# 3w-rgb-led-dongle-mk-1_0.net
KiCad netlist of a schematic drawn in EAGLE
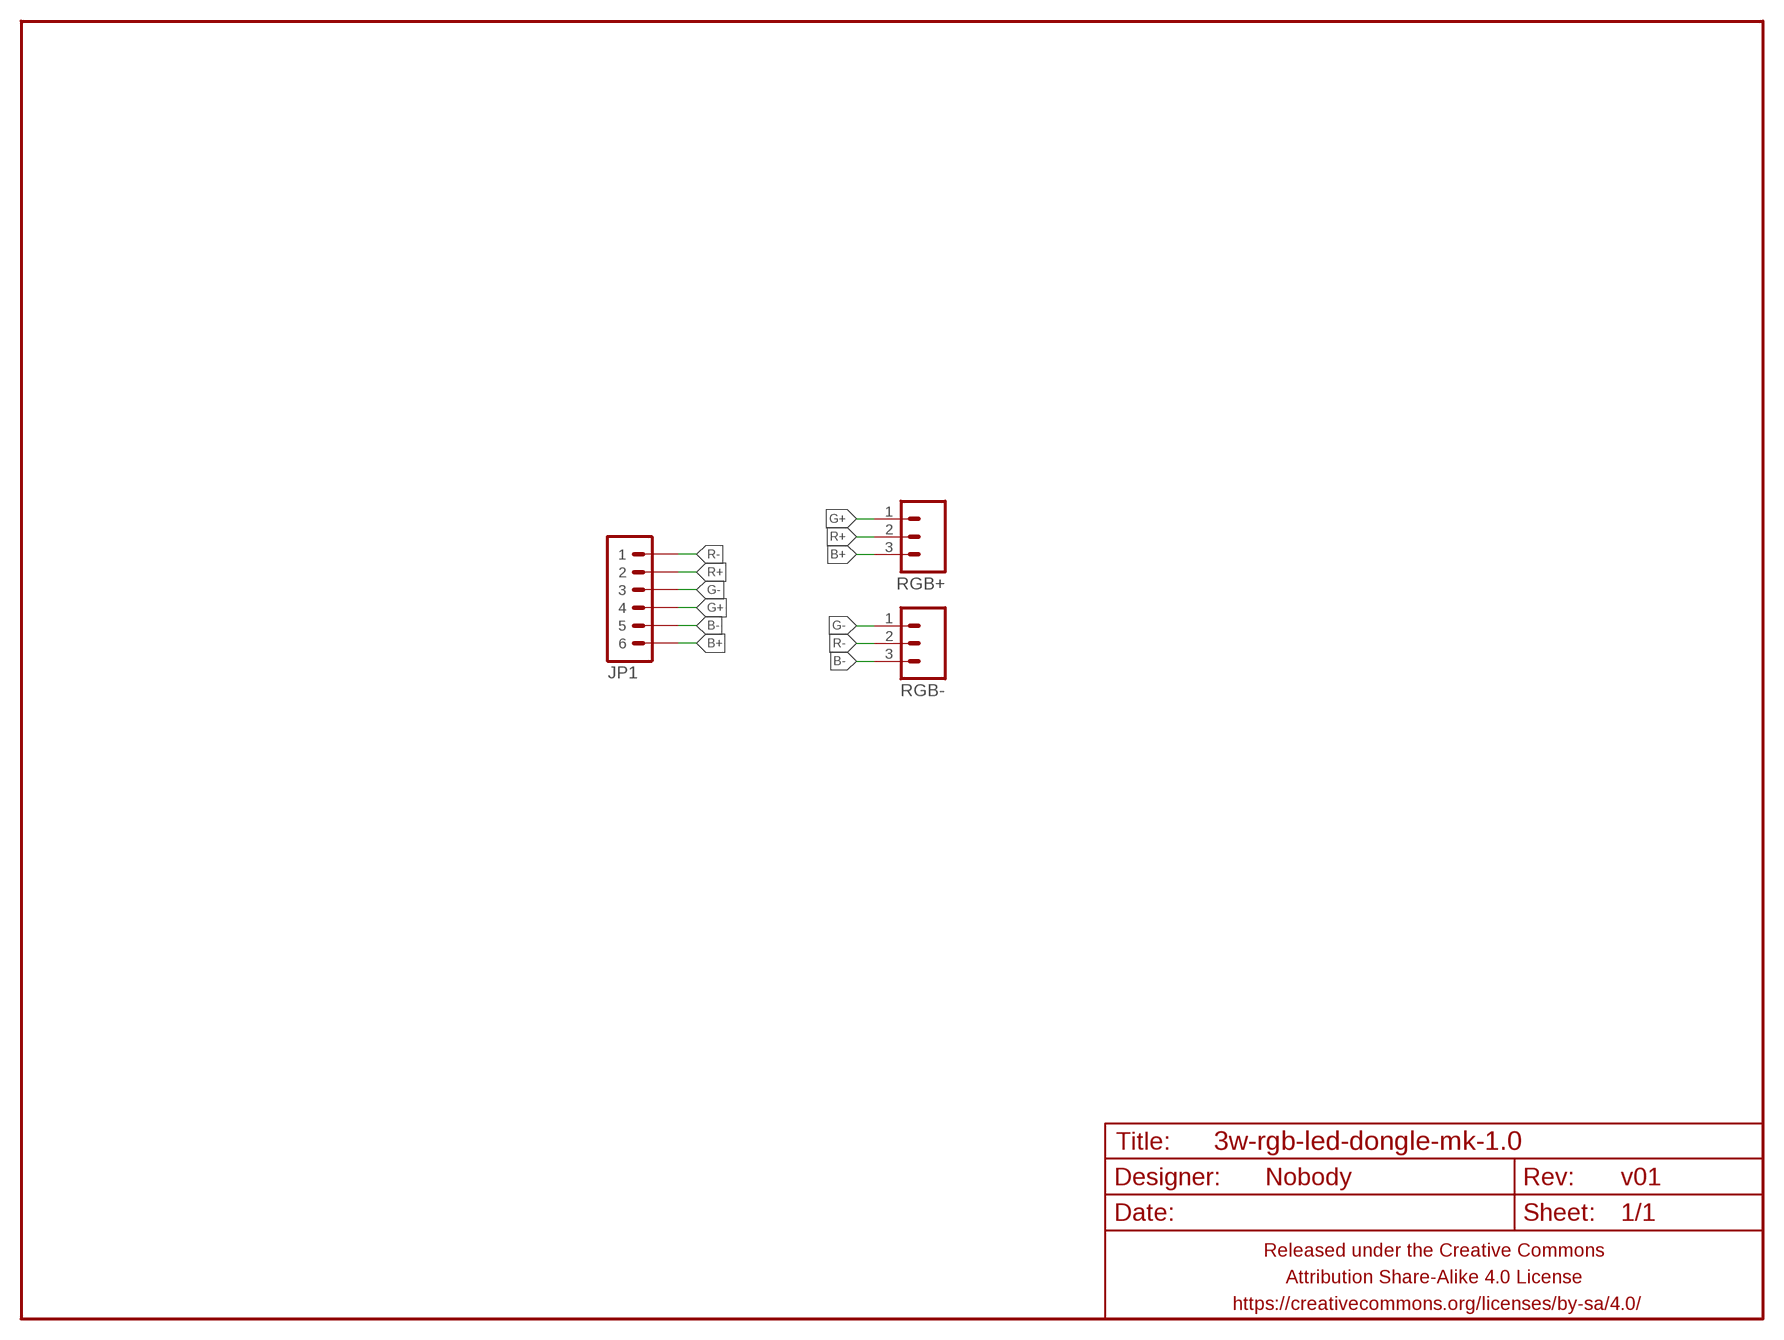
[diagram p0: schematic, sheet 1]

(export (version "E")
  (design (tool "Eeschema 10.0.6"))
  (components
    (comp (ref "FRAME1")
      (value "FRAME-LETTERNO_PACKAGE")
      (footprint "eagle-import:DUMMY")
      (fields (field (name "DESIGNER") "Nobody"))
      (libsource (lib "eagle-import") (part "FRAME-LETTERNO_PACKAGE"))
    )
    (comp (ref "JP1")
      (value "M06JST-XH-RA-PTH-LONG")
      (footprint "eagle-import:1X06-2.5MM-JST-XH-RA-LONG")
      (libsource (lib "eagle-import") (part "M06JST-XH-RA-PTH-LONG"))
    )
    (comp (ref "RGB+")
      (value "M03JST-3-XH-RA-PTH-LONG")
      (footprint "eagle-import:JST-3-XH-RA-PTH-LONG")
      (libsource (lib "eagle-import") (part "M03JST-3-XH-RA-PTH-LONG"))
    )
    (comp (ref "RGB-")
      (value "M03JST-3-XH-RA-PTH-LONG")
      (footprint "eagle-import:JST-3-XH-RA-PTH-LONG")
      (libsource (lib "eagle-import") (part "M03JST-3-XH-RA-PTH-LONG"))
    )
  )
  (nets
    (net (code "1") (name "B+") (class "Default")
      (node (ref "JP1") (pin "6") (pinfunction "6_6") (pintype "passive"))
      (node (ref "RGB+") (pin "3") (pinfunction "3_3") (pintype "passive"))
    )
    (net (code "2") (name "B-") (class "Default")
      (node (ref "JP1") (pin "5") (pinfunction "5_5") (pintype "passive"))
      (node (ref "RGB-") (pin "3") (pinfunction "3_3") (pintype "passive"))
    )
    (net (code "3") (name "G+") (class "Default")
      (node (ref "JP1") (pin "4") (pinfunction "4_4") (pintype "passive"))
      (node (ref "RGB+") (pin "1") (pinfunction "1_1") (pintype "passive"))
    )
    (net (code "4") (name "G-") (class "Default")
      (node (ref "JP1") (pin "3") (pinfunction "3_3") (pintype "passive"))
      (node (ref "RGB-") (pin "1") (pinfunction "1_1") (pintype "passive"))
    )
    (net (code "5") (name "R+") (class "Default")
      (node (ref "JP1") (pin "2") (pinfunction "2_2") (pintype "passive"))
      (node (ref "RGB+") (pin "2") (pinfunction "2_2") (pintype "passive"))
    )
    (net (code "6") (name "R-") (class "Default")
      (node (ref "JP1") (pin "1") (pinfunction "1_1") (pintype "passive"))
      (node (ref "RGB-") (pin "2") (pinfunction "2_2") (pintype "passive"))
    )
  )
)
